# Test.net
KiCad netlist of a schematic drawn in EAGLE
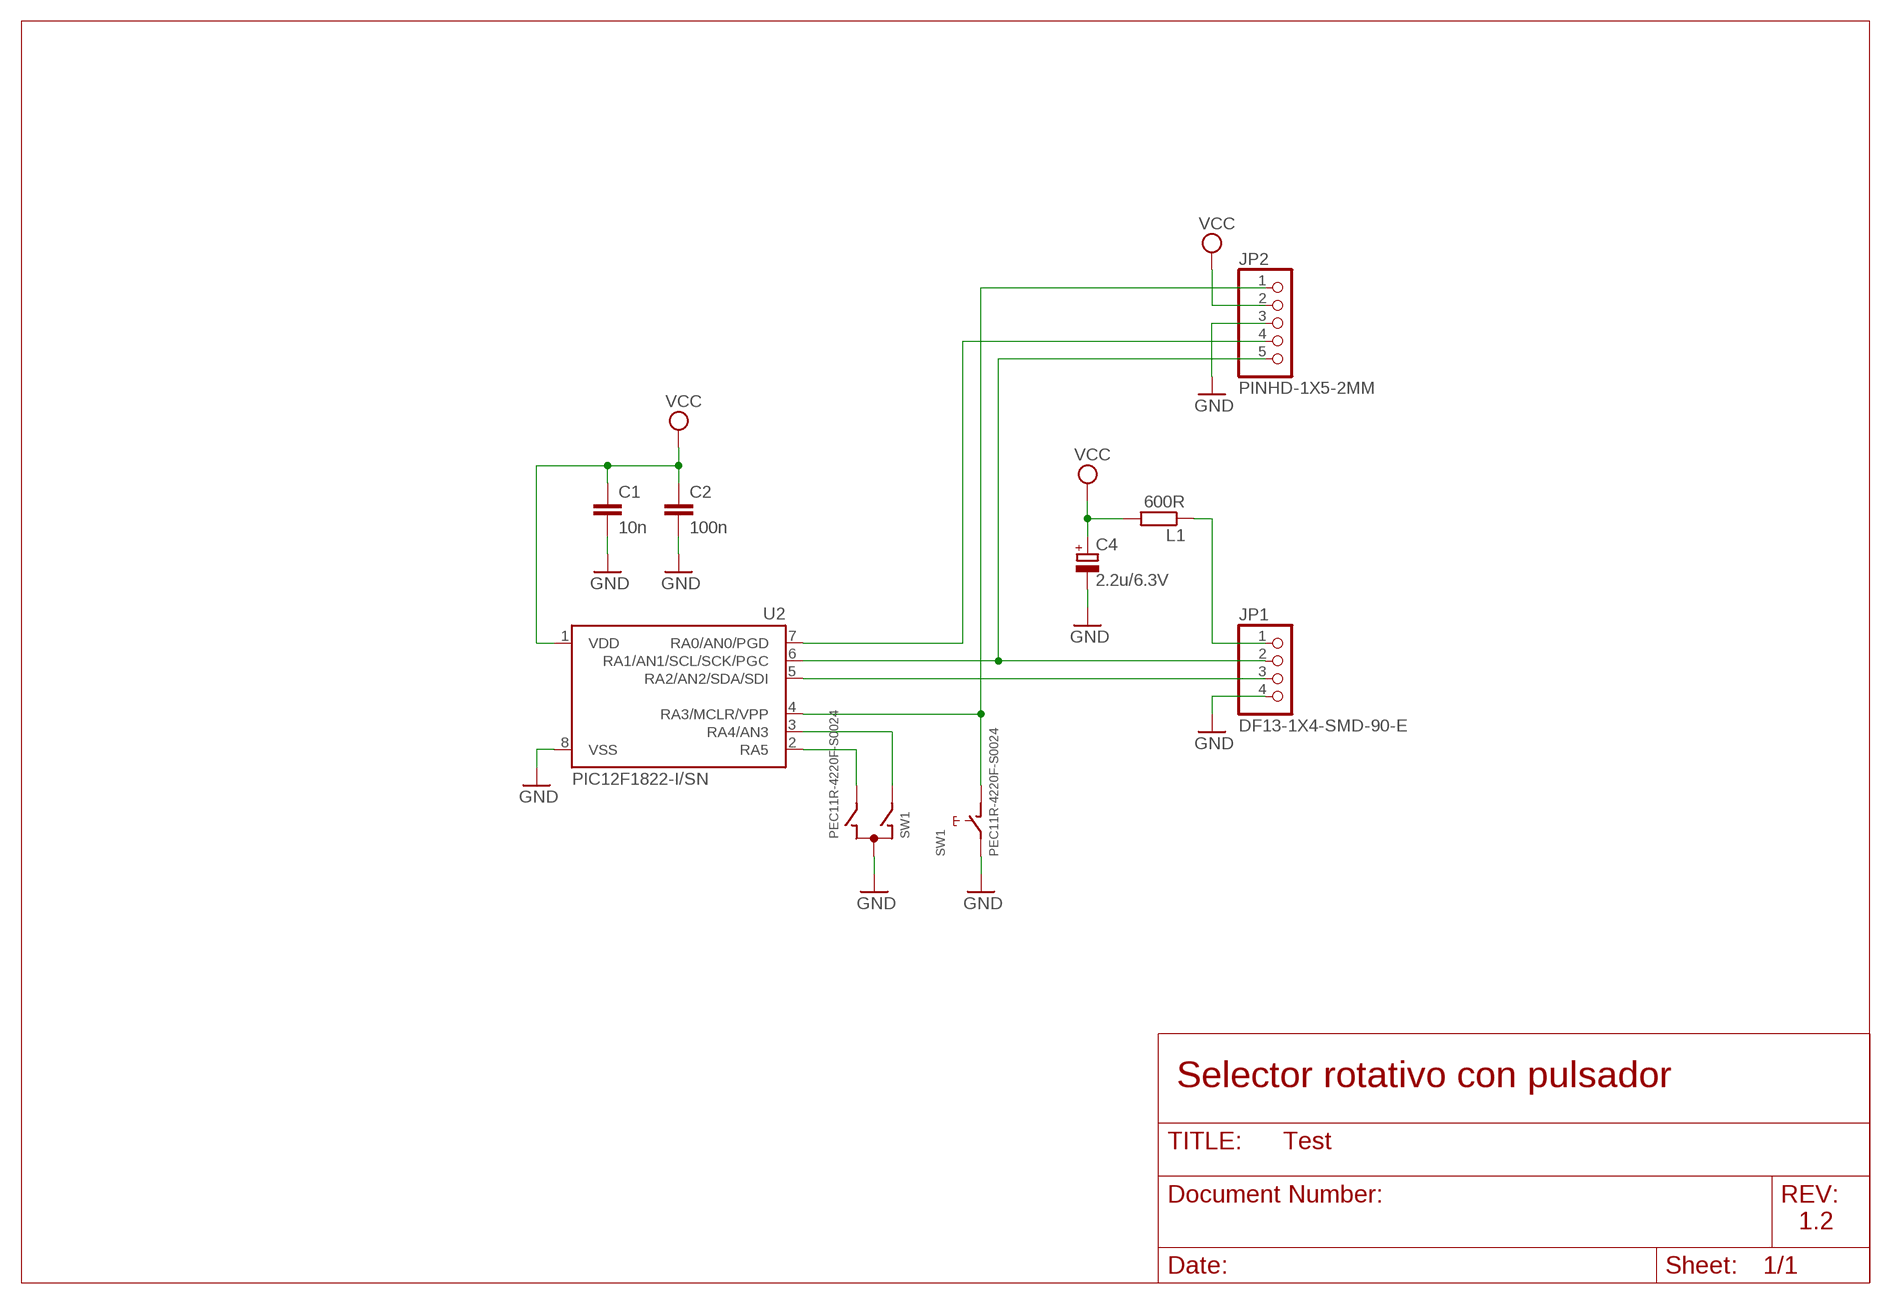
[diagram p0: schematic, sheet 1]

(export (version "E")
  (design (tool "Eeschema 10.0.6"))
  (components
    (comp (ref "C1")
      (value "10n")
      (footprint "eagle-import:C0805")
      (fields (field (name "PROVIDER") "MOUSER"))
      (libsource (lib "eagle-import") (part "C-EUC0805"))
    )
    (comp (ref "C2")
      (value "100n")
      (footprint "eagle-import:C0805")
      (fields (field (name "PROVIDER") "MOUSER"))
      (libsource (lib "eagle-import") (part "C-EUC0805"))
    )
    (comp (ref "C4")
      (value "2.2u/6.3V")
      (footprint "eagle-import:SMC_A")
      (fields (field (name "PROVIDER") "MOUSER"))
      (libsource (lib "eagle-import") (part "CPOL-EUSMCA"))
    )
    (comp (ref "JP1")
      (value "DF13-1X4-SMD-90-E")
      (footprint "eagle-import:1X4-SMD-90-E")
      (fields (field (name "MANUFACTURER") "Hirose Electric") (field (name "PROVIDER") "MOUSER"))
      (libsource (lib "eagle-import") (part "DF13-1X4-SMD-90-E"))
    )
    (comp (ref "JP2")
      (value "PINHD-1X5-2MM")
      (footprint "eagle-import:1X05-2MM")
      (libsource (lib "eagle-import") (part "PINHD-1X5-2MM"))
    )
    (comp (ref "L1")
      (value "600R")
      (footprint "eagle-import:R0805")
      (libsource (lib "eagle-import") (part "R-EU_R0805"))
    )
    (comp (ref "SW1")
      (value "PEC11R-4220F-S0024")
      (footprint "eagle-import:PEC11R")
      (fields (field (name "MANUFACTURER") "BOURNS"))
      (libsource (lib "eagle-import") (part "PEC11R-4220F-S0024"))
    )
    (comp (ref "U2")
      (value "PIC12F1822-I/SN")
      (footprint "eagle-import:SO08")
      (fields (field (name "MANUFACTURER") "Microchip"))
      (libsource (lib "eagle-import") (part "PIC12F1822-I/SN"))
    )
  )
  (nets
    (net (code "1") (name "GND") (class "Default")
      (node (ref "C1") (pin "2") (pinfunction "2_2") (pintype "passive"))
      (node (ref "C2") (pin "2") (pinfunction "2_2") (pintype "passive"))
      (node (ref "C4") (pin "-") (pinfunction "-_-") (pintype "passive"))
      (node (ref "JP1") (pin "4") (pinfunction "4_4") (pintype "passive"))
      (node (ref "JP2") (pin "3") (pinfunction "3_3") (pintype "passive"))
      (node (ref "SW1") (pin "C") (pinfunction "C_C") (pintype "passive"))
      (node (ref "SW1") (pin "E") (pinfunction "2_E") (pintype "passive"))
      (node (ref "U2") (pin "8") (pinfunction "VSS_8") (pintype "power_in"))
    )
    (net (code "2") (name "Net-(JP1-Pad1)") (class "Default")
      (node (ref "JP1") (pin "1") (pinfunction "1_1") (pintype "passive"))
      (node (ref "L1") (pin "1") (pinfunction "1_1") (pintype "passive"))
    )
    (net (code "3") (name "Net-(SW1B-1)") (class "Default")
      (node (ref "JP2") (pin "1") (pinfunction "1_1") (pintype "passive"))
      (node (ref "SW1") (pin "D") (pinfunction "1_D") (pintype "passive"))
      (node (ref "U2") (pin "4") (pinfunction "RA3/MCLR/VPP_4") (pintype "bidirectional"))
    )
    (net (code "4") (name "Net-(U2-RA0{slash}AN0{slash}PGD)") (class "Default")
      (node (ref "JP2") (pin "4") (pinfunction "4_4") (pintype "passive"))
      (node (ref "U2") (pin "7") (pinfunction "RA0/AN0/PGD_7") (pintype "bidirectional"))
    )
    (net (code "5") (name "Net-(U2-RA1{slash}AN1{slash}SCL{slash}SCK{slash}PGC)") (class "Default")
      (node (ref "JP1") (pin "2") (pinfunction "2_2") (pintype "passive"))
      (node (ref "JP2") (pin "5") (pinfunction "5_5") (pintype "passive"))
      (node (ref "U2") (pin "6") (pinfunction "RA1/AN1/SCL/SCK/PGC_6") (pintype "bidirectional"))
    )
    (net (code "6") (name "Net-(U2-RA2{slash}AN2{slash}SDA{slash}SDI)") (class "Default")
      (node (ref "JP1") (pin "3") (pinfunction "3_3") (pintype "passive"))
      (node (ref "U2") (pin "5") (pinfunction "RA2/AN2/SDA/SDI_5") (pintype "bidirectional"))
    )
    (net (code "7") (name "Net-(U2-RA4{slash}AN3)") (class "Default")
      (node (ref "SW1") (pin "A") (pinfunction "A_A") (pintype "passive"))
      (node (ref "U2") (pin "3") (pinfunction "RA4/AN3_3") (pintype "bidirectional"))
    )
    (net (code "8") (name "Net-(U2-RA5)") (class "Default")
      (node (ref "SW1") (pin "B") (pinfunction "B_B") (pintype "passive"))
      (node (ref "U2") (pin "2") (pinfunction "RA5_2") (pintype "bidirectional"))
    )
    (net (code "9") (name "VCC") (class "Default")
      (node (ref "C1") (pin "1") (pinfunction "1_1") (pintype "passive"))
      (node (ref "C2") (pin "1") (pinfunction "1_1") (pintype "passive"))
      (node (ref "C4") (pin "+") (pinfunction "+_+") (pintype "passive"))
      (node (ref "JP2") (pin "2") (pinfunction "2_2") (pintype "passive"))
      (node (ref "L1") (pin "2") (pinfunction "2_2") (pintype "passive"))
      (node (ref "U2") (pin "1") (pinfunction "VDD_1") (pintype "power_in"))
    )
  )
)
